# node-lite.net
KiCad netlist of a schematic drawn in EAGLE
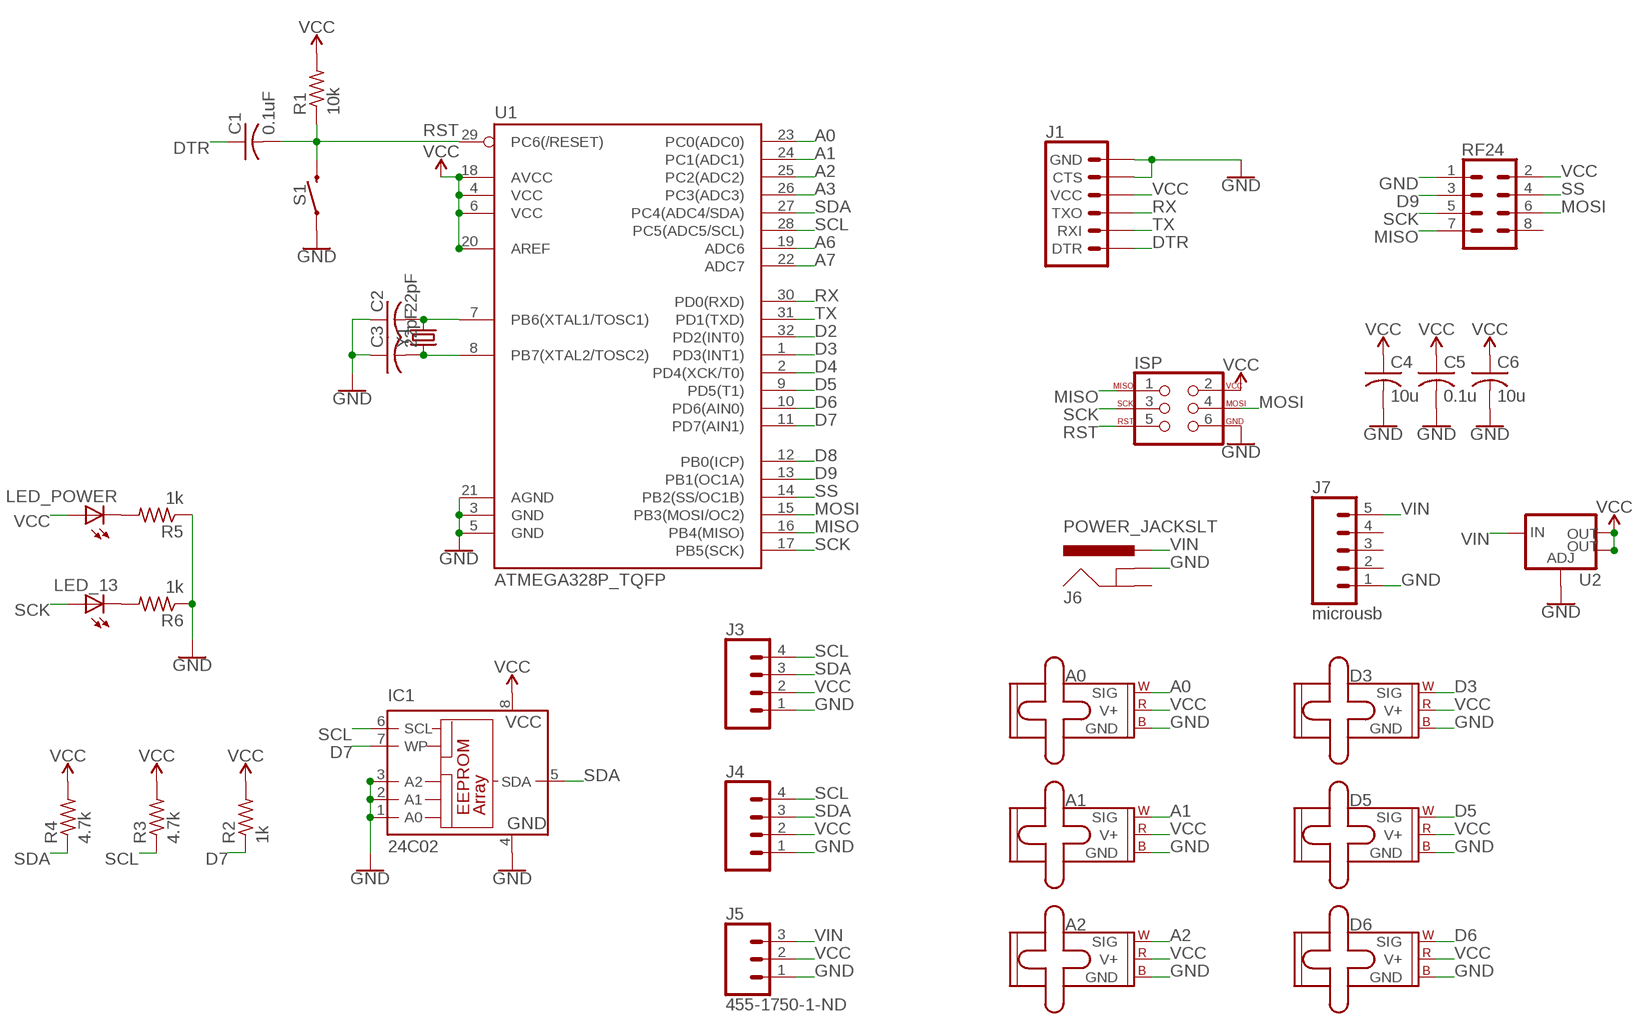
[diagram p0: schematic, sheet 1]

(export (version "E")
  (design (tool "Eeschema 10.0.6"))
  (components
    (comp (ref "A0")
      (value "SERVO")
      (footprint "eagle-import:1X03")
      (libsource (lib "eagle-import") (part "SERVO"))
    )
    (comp (ref "A1")
      (value "SERVO")
      (footprint "eagle-import:1X03")
      (libsource (lib "eagle-import") (part "SERVO"))
    )
    (comp (ref "A2")
      (value "SERVO")
      (footprint "eagle-import:1X03")
      (libsource (lib "eagle-import") (part "SERVO"))
    )
    (comp (ref "C1")
      (value "0.1uF")
      (footprint "eagle-import:C1206")
      (libsource (lib "eagle-import") (part "C-USC1206"))
    )
    (comp (ref "C2")
      (value "22pF")
      (footprint "eagle-import:C1206")
      (libsource (lib "eagle-import") (part "C-USC1206"))
    )
    (comp (ref "C3")
      (value "22pF")
      (footprint "eagle-import:C1206")
      (libsource (lib "eagle-import") (part "C-USC1206"))
    )
    (comp (ref "C4")
      (value "10u")
      (footprint "eagle-import:C1206")
      (libsource (lib "eagle-import") (part "C-USC1206"))
    )
    (comp (ref "C5")
      (value "0.1u")
      (footprint "eagle-import:C1206")
      (libsource (lib "eagle-import") (part "C-USC1206"))
    )
    (comp (ref "C6")
      (value "10u")
      (footprint "eagle-import:C1206")
      (libsource (lib "eagle-import") (part "C-USC1206"))
    )
    (comp (ref "D3")
      (value "SERVO")
      (footprint "eagle-import:1X03")
      (libsource (lib "eagle-import") (part "SERVO"))
    )
    (comp (ref "D5")
      (value "SERVO")
      (footprint "eagle-import:1X03")
      (libsource (lib "eagle-import") (part "SERVO"))
    )
    (comp (ref "D6")
      (value "SERVO")
      (footprint "eagle-import:1X03")
      (libsource (lib "eagle-import") (part "SERVO"))
    )
    (comp (ref "IC1")
      (value "24C02")
      (footprint "eagle-import:SO-08")
      (libsource (lib "eagle-import") (part "24CSN02A"))
    )
    (comp (ref "ISP")
      (value "AVR_SPI_PROG_3X2NS")
      (footprint "eagle-import:2X3-NS")
      (libsource (lib "eagle-import") (part "AVR_SPI_PROG_3X2NS"))
    )
    (comp (ref "J1")
      (value "6_PIN_SERIAL_TARGET")
      (footprint "eagle-import:1X06")
      (libsource (lib "eagle-import") (part "6_PIN_SERIAL_TARGET"))
    )
    (comp (ref "J3")
      (value "CONN_04")
      (footprint "eagle-import:1X04")
      (libsource (lib "eagle-import") (part "CONN_04"))
    )
    (comp (ref "J4")
      (value "CONN_04")
      (footprint "eagle-import:1X04")
      (libsource (lib "eagle-import") (part "CONN_04"))
    )
    (comp (ref "J5")
      (value "455-1750-1-ND")
      (footprint "eagle-import:1X03")
      (libsource (lib "eagle-import") (part "CONN_03"))
    )
    (comp (ref "J6")
      (value "POWER_JACKSLT")
      (footprint "eagle-import:POWER_JACK_SLOT")
      (libsource (lib "eagle-import") (part "POWER_JACKSLT"))
    )
    (comp (ref "J7")
      (value "microusb")
      (footprint "eagle-import:1X05")
      (libsource (lib "eagle-import") (part "CONN_05"))
    )
    (comp (ref "LED_13")
      (value "LEDCHIPLED_1206")
      (footprint "eagle-import:CHIPLED_1206")
      (libsource (lib "eagle-import") (part "LEDCHIPLED_1206"))
    )
    (comp (ref "LED_POWER")
      (value "LEDCHIPLED_1206")
      (footprint "eagle-import:CHIPLED_1206")
      (libsource (lib "eagle-import") (part "LEDCHIPLED_1206"))
    )
    (comp (ref "R1")
      (value "10k")
      (footprint "eagle-import:R1206")
      (libsource (lib "eagle-import") (part "R-US_R1206"))
    )
    (comp (ref "R2")
      (value "1k")
      (footprint "eagle-import:R1206")
      (libsource (lib "eagle-import") (part "R-US_R1206"))
    )
    (comp (ref "R3")
      (value "4.7k")
      (footprint "eagle-import:R1206")
      (libsource (lib "eagle-import") (part "R-US_R1206"))
    )
    (comp (ref "R4")
      (value "4.7k")
      (footprint "eagle-import:R1206")
      (libsource (lib "eagle-import") (part "R-US_R1206"))
    )
    (comp (ref "R5")
      (value "1k")
      (footprint "eagle-import:R1206")
      (libsource (lib "eagle-import") (part "R-US_R1206"))
    )
    (comp (ref "R6")
      (value "1k")
      (footprint "eagle-import:R1206")
      (libsource (lib "eagle-import") (part "R-US_R1206"))
    )
    (comp (ref "RF24")
      (value "CONN_04X2")
      (footprint "eagle-import:2X4")
      (libsource (lib "eagle-import") (part "CONN_04X2"))
    )
    (comp (ref "S1")
      (value "MOMENTARY-SWITCH-SPST-PTH-6.0MM")
      (footprint "eagle-import:TACTILE_SWITCH_PTH_6.0MM")
      (libsource (lib "eagle-import") (part "MOMENTARY-SWITCH-SPST-PTH-6.0MM"))
    )
    (comp (ref "U1")
      (value "ATMEGA328P_TQFP")
      (footprint "eagle-import:TQFP32-08")
      (libsource (lib "eagle-import") (part "ATMEGA328P_TQFP"))
    )
    (comp (ref "U2")
      (value "V_REG_LM1117SOT223")
      (footprint "eagle-import:SOT223")
      (libsource (lib "eagle-import") (part "V_REG_LM1117SOT223"))
    )
    (comp (ref "Y1")
      (value "CRYSTALPTH-HC49US")
      (footprint "eagle-import:HC49US")
      (libsource (lib "eagle-import") (part "CRYSTALPTH-HC49US"))
    )
  )
  (nets
    (net (code "1") (name "/A0") (class "Default")
      (node (ref "A0") (pin "1") (pinfunction "SIG_1") (pintype "bidirectional"))
      (node (ref "U1") (pin "23") (pinfunction "PC0(ADC0)_23") (pintype "bidirectional"))
    )
    (net (code "2") (name "/A1") (class "Default")
      (node (ref "A1") (pin "1") (pinfunction "SIG_1") (pintype "bidirectional"))
      (node (ref "U1") (pin "24") (pinfunction "PC1(ADC1)_24") (pintype "bidirectional"))
    )
    (net (code "3") (name "/A2") (class "Default")
      (node (ref "A2") (pin "1") (pinfunction "SIG_1") (pintype "bidirectional"))
      (node (ref "U1") (pin "25") (pinfunction "PC2(ADC2)_25") (pintype "bidirectional"))
    )
    (net (code "4") (name "/A3") (class "Default")
      (node (ref "U1") (pin "26") (pinfunction "PC3(ADC3)_26") (pintype "bidirectional"))
    )
    (net (code "5") (name "/A6") (class "Default")
      (node (ref "U1") (pin "19") (pinfunction "ADC6_19") (pintype "bidirectional"))
    )
    (net (code "6") (name "/A7") (class "Default")
      (node (ref "U1") (pin "22") (pinfunction "ADC7_22") (pintype "bidirectional"))
    )
    (net (code "7") (name "/D2") (class "Default")
      (node (ref "U1") (pin "32") (pinfunction "PD2(INT0)_32") (pintype "bidirectional"))
    )
    (net (code "8") (name "/D3") (class "Default")
      (node (ref "D3") (pin "1") (pinfunction "SIG_1") (pintype "bidirectional"))
      (node (ref "U1") (pin "1") (pinfunction "PD3(INT1)_1") (pintype "bidirectional"))
    )
    (net (code "9") (name "/D4") (class "Default")
      (node (ref "U1") (pin "2") (pinfunction "PD4(XCK/T0)_2") (pintype "bidirectional"))
    )
    (net (code "10") (name "/D5") (class "Default")
      (node (ref "D5") (pin "1") (pinfunction "SIG_1") (pintype "bidirectional"))
      (node (ref "U1") (pin "9") (pinfunction "PD5(T1)_9") (pintype "bidirectional"))
    )
    (net (code "11") (name "/D6") (class "Default")
      (node (ref "D6") (pin "1") (pinfunction "SIG_1") (pintype "bidirectional"))
      (node (ref "U1") (pin "10") (pinfunction "PD6(AIN0)_10") (pintype "bidirectional"))
    )
    (net (code "12") (name "/D7") (class "Default")
      (node (ref "IC1") (pin "7") (pinfunction "WP_7") (pintype "input"))
      (node (ref "R2") (pin "1") (pinfunction "1_1") (pintype "passive"))
      (node (ref "U1") (pin "11") (pinfunction "PD7(AIN1)_11") (pintype "bidirectional"))
    )
    (net (code "13") (name "/D8") (class "Default")
      (node (ref "U1") (pin "12") (pinfunction "PB0(ICP)_12") (pintype "bidirectional"))
    )
    (net (code "14") (name "/D9") (class "Default")
      (node (ref "RF24") (pin "3") (pinfunction "3_3") (pintype "passive"))
      (node (ref "U1") (pin "13") (pinfunction "PB1(OC1A)_13") (pintype "bidirectional"))
    )
    (net (code "15") (name "/DTR") (class "Default")
      (node (ref "C1") (pin "1") (pinfunction "1_1") (pintype "passive"))
      (node (ref "J1") (pin "1") (pinfunction "DTR_1") (pintype "passive"))
    )
    (net (code "16") (name "/MISO") (class "Default")
      (node (ref "ISP") (pin "1") (pinfunction "1_1") (pintype "passive"))
      (node (ref "RF24") (pin "7") (pinfunction "7_7") (pintype "passive"))
      (node (ref "U1") (pin "16") (pinfunction "PB4(MISO)_16") (pintype "bidirectional"))
    )
    (net (code "17") (name "/MOSI") (class "Default")
      (node (ref "ISP") (pin "4") (pinfunction "4_4") (pintype "passive"))
      (node (ref "RF24") (pin "6") (pinfunction "6_6") (pintype "passive"))
      (node (ref "U1") (pin "15") (pinfunction "PB3(MOSI/OC2)_15") (pintype "bidirectional"))
    )
    (net (code "18") (name "/RST") (class "Default")
      (node (ref "C1") (pin "2") (pinfunction "2_2") (pintype "passive"))
      (node (ref "ISP") (pin "5") (pinfunction "5_5") (pintype "passive"))
      (node (ref "R1") (pin "1") (pinfunction "1_1") (pintype "passive"))
      (node (ref "S1") (pin "3") (pinfunction "2_3") (pintype "passive"))
      (node (ref "U1") (pin "29") (pinfunction "PC6(/RESET)_29") (pintype "bidirectional"))
    )
    (net (code "19") (name "/RX") (class "Default")
      (node (ref "J1") (pin "3") (pinfunction "TXO_3") (pintype "passive"))
      (node (ref "U1") (pin "30") (pinfunction "PD0(RXD)_30") (pintype "bidirectional"))
    )
    (net (code "20") (name "/SCK") (class "Default")
      (node (ref "ISP") (pin "3") (pinfunction "3_3") (pintype "passive"))
      (node (ref "LED_13") (pin "A") (pinfunction "A_A") (pintype "passive"))
      (node (ref "RF24") (pin "5") (pinfunction "5_5") (pintype "passive"))
      (node (ref "U1") (pin "17") (pinfunction "PB5(SCK)_17") (pintype "bidirectional"))
    )
    (net (code "21") (name "/SCL") (class "Default")
      (node (ref "IC1") (pin "6") (pinfunction "SCL_6") (pintype "input"))
      (node (ref "J3") (pin "4") (pinfunction "4_4") (pintype "passive"))
      (node (ref "J4") (pin "4") (pinfunction "4_4") (pintype "passive"))
      (node (ref "R3") (pin "1") (pinfunction "1_1") (pintype "passive"))
      (node (ref "U1") (pin "28") (pinfunction "PC5(ADC5/SCL)_28") (pintype "bidirectional"))
    )
    (net (code "22") (name "/SDA") (class "Default")
      (node (ref "IC1") (pin "5") (pinfunction "SDA_5") (pintype "bidirectional"))
      (node (ref "J3") (pin "3") (pinfunction "3_3") (pintype "passive"))
      (node (ref "J4") (pin "3") (pinfunction "3_3") (pintype "passive"))
      (node (ref "R4") (pin "1") (pinfunction "1_1") (pintype "passive"))
      (node (ref "U1") (pin "27") (pinfunction "PC4(ADC4/SDA)_27") (pintype "bidirectional"))
    )
    (net (code "23") (name "/SS") (class "Default")
      (node (ref "RF24") (pin "4") (pinfunction "4_4") (pintype "passive"))
      (node (ref "U1") (pin "14") (pinfunction "PB2(SS/OC1B)_14") (pintype "bidirectional"))
    )
    (net (code "24") (name "/TX") (class "Default")
      (node (ref "J1") (pin "2") (pinfunction "RXI_2") (pintype "passive"))
      (node (ref "U1") (pin "31") (pinfunction "PD1(TXD)_31") (pintype "bidirectional"))
    )
    (net (code "25") (name "/VIN") (class "Default")
      (node (ref "J5") (pin "3") (pinfunction "3_3") (pintype "passive"))
      (node (ref "J6") (pin "PWR") (pinfunction "PWR_PWR") (pintype "bidirectional"))
      (node (ref "J7") (pin "5") (pinfunction "5_5") (pintype "passive"))
      (node (ref "U2") (pin "3") (pinfunction "IN_3") (pintype "input"))
    )
    (net (code "26") (name "GND") (class "Default")
      (node (ref "A0") (pin "3") (pinfunction "GND_3") (pintype "bidirectional"))
      (node (ref "A1") (pin "3") (pinfunction "GND_3") (pintype "bidirectional"))
      (node (ref "A2") (pin "3") (pinfunction "GND_3") (pintype "bidirectional"))
      (node (ref "C2") (pin "1") (pinfunction "1_1") (pintype "passive"))
      (node (ref "C3") (pin "1") (pinfunction "1_1") (pintype "passive"))
      (node (ref "C4") (pin "2") (pinfunction "2_2") (pintype "passive"))
      (node (ref "C5") (pin "2") (pinfunction "2_2") (pintype "passive"))
      (node (ref "C6") (pin "2") (pinfunction "2_2") (pintype "passive"))
      (node (ref "D3") (pin "3") (pinfunction "GND_3") (pintype "bidirectional"))
      (node (ref "D5") (pin "3") (pinfunction "GND_3") (pintype "bidirectional"))
      (node (ref "D6") (pin "3") (pinfunction "GND_3") (pintype "bidirectional"))
      (node (ref "IC1") (pin "1") (pinfunction "A0_1") (pintype "input"))
      (node (ref "IC1") (pin "2") (pinfunction "A1_2") (pintype "input"))
      (node (ref "IC1") (pin "3") (pinfunction "A2_3") (pintype "input"))
      (node (ref "IC1") (pin "4") (pinfunction "GND_4") (pintype "power_in"))
      (node (ref "ISP") (pin "6") (pinfunction "6_6") (pintype "passive"))
      (node (ref "J1") (pin "5") (pinfunction "CTS_5") (pintype "passive"))
      (node (ref "J1") (pin "6") (pinfunction "GND_6") (pintype "passive"))
      (node (ref "J3") (pin "1") (pinfunction "1_1") (pintype "passive"))
      (node (ref "J4") (pin "1") (pinfunction "1_1") (pintype "passive"))
      (node (ref "J5") (pin "1") (pinfunction "1_1") (pintype "passive"))
      (node (ref "J6") (pin "GND@1") (pinfunction "GNDBREAK_GND@1") (pintype "bidirectional"))
      (node (ref "J7") (pin "1") (pinfunction "1_1") (pintype "passive"))
      (node (ref "R5") (pin "1") (pinfunction "1_1") (pintype "passive"))
      (node (ref "R6") (pin "1") (pinfunction "1_1") (pintype "passive"))
      (node (ref "RF24") (pin "1") (pinfunction "1_1") (pintype "passive"))
      (node (ref "S1") (pin "1") (pinfunction "1_1") (pintype "passive"))
      (node (ref "U1") (pin "21") (pinfunction "AGND_21") (pintype "bidirectional"))
      (node (ref "U1") (pin "3") (pinfunction "GND_3") (pintype "bidirectional"))
      (node (ref "U1") (pin "5") (pinfunction "GND_5") (pintype "bidirectional"))
      (node (ref "U2") (pin "1") (pinfunction "ADJ_1") (pintype "input"))
    )
    (net (code "27") (name "Net-(LED_13-PadC)") (class "Default")
      (node (ref "LED_13") (pin "C") (pinfunction "C_C") (pintype "passive"))
      (node (ref "R6") (pin "2") (pinfunction "2_2") (pintype "passive"))
    )
    (net (code "28") (name "Net-(LED_POWER-PadC)") (class "Default")
      (node (ref "LED_POWER") (pin "C") (pinfunction "C_C") (pintype "passive"))
      (node (ref "R5") (pin "2") (pinfunction "2_2") (pintype "passive"))
    )
    (net (code "29") (name "Net-(U1-PB6(XTAL1{slash}TOSC1))") (class "Default")
      (node (ref "C2") (pin "2") (pinfunction "2_2") (pintype "passive"))
      (node (ref "U1") (pin "7") (pinfunction "PB6(XTAL1/TOSC1)_7") (pintype "bidirectional"))
      (node (ref "Y1") (pin "2") (pinfunction "2_2") (pintype "passive"))
    )
    (net (code "30") (name "Net-(U1-PB7(XTAL2{slash}TOSC2))") (class "Default")
      (node (ref "C3") (pin "2") (pinfunction "2_2") (pintype "passive"))
      (node (ref "U1") (pin "8") (pinfunction "PB7(XTAL2/TOSC2)_8") (pintype "bidirectional"))
      (node (ref "Y1") (pin "1") (pinfunction "1_1") (pintype "passive"))
    )
    (net (code "31") (name "VCC") (class "Default")
      (node (ref "A0") (pin "2") (pinfunction "V+_2") (pintype "bidirectional"))
      (node (ref "A1") (pin "2") (pinfunction "V+_2") (pintype "bidirectional"))
      (node (ref "A2") (pin "2") (pinfunction "V+_2") (pintype "bidirectional"))
      (node (ref "C4") (pin "1") (pinfunction "1_1") (pintype "passive"))
      (node (ref "C5") (pin "1") (pinfunction "1_1") (pintype "passive"))
      (node (ref "C6") (pin "1") (pinfunction "1_1") (pintype "passive"))
      (node (ref "D3") (pin "2") (pinfunction "V+_2") (pintype "bidirectional"))
      (node (ref "D5") (pin "2") (pinfunction "V+_2") (pintype "bidirectional"))
      (node (ref "D6") (pin "2") (pinfunction "V+_2") (pintype "bidirectional"))
      (node (ref "IC1") (pin "8") (pinfunction "VCC_8") (pintype "power_in"))
      (node (ref "ISP") (pin "2") (pinfunction "2_2") (pintype "passive"))
      (node (ref "J1") (pin "4") (pinfunction "VCC_4") (pintype "passive"))
      (node (ref "J3") (pin "2") (pinfunction "2_2") (pintype "passive"))
      (node (ref "J4") (pin "2") (pinfunction "2_2") (pintype "passive"))
      (node (ref "J5") (pin "2") (pinfunction "2_2") (pintype "passive"))
      (node (ref "LED_POWER") (pin "A") (pinfunction "A_A") (pintype "passive"))
      (node (ref "R1") (pin "2") (pinfunction "2_2") (pintype "passive"))
      (node (ref "R2") (pin "2") (pinfunction "2_2") (pintype "passive"))
      (node (ref "R3") (pin "2") (pinfunction "2_2") (pintype "passive"))
      (node (ref "R4") (pin "2") (pinfunction "2_2") (pintype "passive"))
      (node (ref "RF24") (pin "2") (pinfunction "2_2") (pintype "passive"))
      (node (ref "U1") (pin "18") (pinfunction "AVCC_18") (pintype "bidirectional"))
      (node (ref "U1") (pin "20") (pinfunction "AREF_20") (pintype "bidirectional"))
      (node (ref "U1") (pin "4") (pinfunction "VCC_4") (pintype "bidirectional"))
      (node (ref "U1") (pin "6") (pinfunction "VCC_6") (pintype "bidirectional"))
      (node (ref "U2") (pin "2") (pinfunction "OUT_2") (pintype "output"))
      (node (ref "U2") (pin "4") (pinfunction "OUT_4") (pintype "output"))
    )
    (net (code "32") (name "unconnected-(J6-GND-PadGND@2)") (class "Default")
      (node (ref "J6") (pin "GND@2") (pinfunction "GND_GND@2") (pintype "bidirectional"))
    )
    (net (code "33") (name "unconnected-(J7-Pad2)") (class "Default")
      (node (ref "J7") (pin "2") (pinfunction "2_2") (pintype "passive"))
    )
    (net (code "34") (name "unconnected-(J7-Pad3)") (class "Default")
      (node (ref "J7") (pin "3") (pinfunction "3_3") (pintype "passive"))
    )
    (net (code "35") (name "unconnected-(J7-Pad4)") (class "Default")
      (node (ref "J7") (pin "4") (pinfunction "4_4") (pintype "passive"))
    )
    (net (code "36") (name "unconnected-(RF24-Pad8)") (class "Default")
      (node (ref "RF24") (pin "8") (pinfunction "8_8") (pintype "passive"))
    )
  )
)
